# qec_pcb_v4.net
KiCad netlist of a schematic drawn in EAGLE
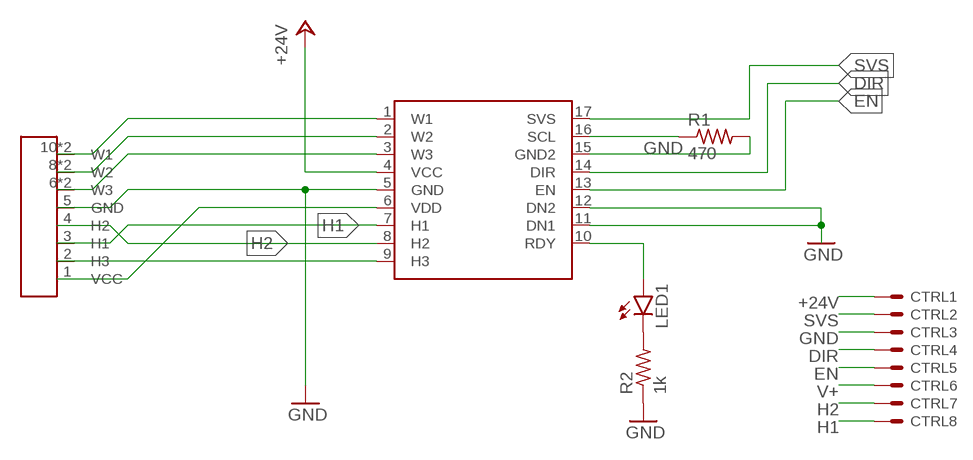
[diagram p0: schematic, sheet 1]

(export (version "E")
  (design (tool "Eeschema 10.0.6"))
  (components
    (comp (ref "CTRL")
      (value "JST8")
      (footprint "eagle-import:JST")
      (libsource (lib "eagle-import") (part "JST8"))
    )
    (comp (ref "DEC")
      (value "1-Q-EC1-Q-EC-SMD")
      (footprint "eagle-import:1-Q-EC-SMD")
      (libsource (lib "eagle-import") (part "1-Q-EC1-Q-EC-SMD"))
    )
    (comp (ref "LED1")
      (value "LEDCHIPLED_0805")
      (footprint "eagle-import:CHIPLED_0805")
      (libsource (lib "eagle-import") (part "LEDCHIPLED_0805"))
    )
    (comp (ref "MOTOR")
      (value "68611114122")
      (footprint "eagle-import:68611114122")
      (libsource (lib "eagle-import") (part "68611114122"))
    )
    (comp (ref "R1")
      (value "470")
      (footprint "eagle-import:M0805")
      (libsource (lib "eagle-import") (part "R-US_M0805"))
    )
    (comp (ref "R2")
      (value "1k")
      (footprint "eagle-import:M0805")
      (libsource (lib "eagle-import") (part "R-US_M0805"))
    )
  )
  (nets
    (net (code "1") (name "+24V") (class "Default")
      (node (ref "CTRL") (pin "1") (pinfunction "S_1") (pintype "passive"))
      (node (ref "DEC") (pin "4") (pinfunction "VCC_4") (pintype "bidirectional"))
    )
    (net (code "2") (name "/V+") (class "Default")
      (node (ref "CTRL") (pin "6") (pinfunction "S_6") (pintype "passive"))
      (node (ref "DEC") (pin "6") (pinfunction "VDD_6") (pintype "bidirectional"))
      (node (ref "MOTOR") (pin "1") (pinfunction "VCC_1") (pintype "bidirectional"))
    )
    (net (code "3") (name "DIR") (class "Default")
      (node (ref "CTRL") (pin "4") (pinfunction "S_4") (pintype "passive"))
      (node (ref "DEC") (pin "14") (pinfunction "DIR_14") (pintype "bidirectional"))
    )
    (net (code "4") (name "EN") (class "Default")
      (node (ref "CTRL") (pin "5") (pinfunction "S_5") (pintype "passive"))
      (node (ref "DEC") (pin "13") (pinfunction "EN_13") (pintype "bidirectional"))
    )
    (net (code "5") (name "GND") (class "Default")
      (node (ref "CTRL") (pin "3") (pinfunction "S_3") (pintype "passive"))
      (node (ref "DEC") (pin "11") (pinfunction "DN1_11") (pintype "bidirectional"))
      (node (ref "DEC") (pin "12") (pinfunction "DN2_12") (pintype "bidirectional"))
      (node (ref "DEC") (pin "15") (pinfunction "GND2_15") (pintype "bidirectional"))
      (node (ref "DEC") (pin "5") (pinfunction "GND_5") (pintype "bidirectional"))
      (node (ref "MOTOR") (pin "5") (pinfunction "GND_5") (pintype "bidirectional"))
      (node (ref "R1") (pin "2") (pinfunction "2_2") (pintype "passive"))
      (node (ref "R2") (pin "1") (pinfunction "1_1") (pintype "passive"))
    )
    (net (code "6") (name "H1") (class "Default")
      (node (ref "CTRL") (pin "8") (pinfunction "S_8") (pintype "passive"))
      (node (ref "DEC") (pin "7") (pinfunction "H1_7") (pintype "bidirectional"))
      (node (ref "MOTOR") (pin "3") (pinfunction "H1_3") (pintype "bidirectional"))
    )
    (net (code "7") (name "H2") (class "Default")
      (node (ref "CTRL") (pin "7") (pinfunction "S_7") (pintype "passive"))
      (node (ref "DEC") (pin "8") (pinfunction "H2_8") (pintype "bidirectional"))
      (node (ref "MOTOR") (pin "4") (pinfunction "H2_4") (pintype "bidirectional"))
    )
    (net (code "8") (name "Net-(DEC-H3)") (class "Default")
      (node (ref "DEC") (pin "9") (pinfunction "H3_9") (pintype "bidirectional"))
      (node (ref "MOTOR") (pin "2") (pinfunction "H3_2") (pintype "bidirectional"))
    )
    (net (code "9") (name "Net-(DEC-RDY)") (class "Default")
      (node (ref "DEC") (pin "10") (pinfunction "RDY_10") (pintype "bidirectional"))
      (node (ref "LED1") (pin "A") (pinfunction "A_A") (pintype "passive"))
    )
    (net (code "10") (name "Net-(DEC-SCL)") (class "Default")
      (node (ref "DEC") (pin "16") (pinfunction "SCL_16") (pintype "bidirectional"))
      (node (ref "R1") (pin "1") (pinfunction "1_1") (pintype "passive"))
    )
    (net (code "11") (name "Net-(DEC-W1)") (class "Default")
      (node (ref "DEC") (pin "1") (pinfunction "W1_1") (pintype "bidirectional"))
      (node (ref "MOTOR") (pin "10") (pinfunction "W1_10") (pintype "bidirectional"))
      (node (ref "MOTOR") (pin "11") (pinfunction "W1_11") (pintype "bidirectional"))
    )
    (net (code "12") (name "Net-(DEC-W2)") (class "Default")
      (node (ref "DEC") (pin "2") (pinfunction "W2_2") (pintype "bidirectional"))
      (node (ref "MOTOR") (pin "8") (pinfunction "W2_8") (pintype "bidirectional"))
      (node (ref "MOTOR") (pin "9") (pinfunction "W2_9") (pintype "bidirectional"))
    )
    (net (code "13") (name "Net-(DEC-W3)") (class "Default")
      (node (ref "DEC") (pin "3") (pinfunction "W3_3") (pintype "bidirectional"))
      (node (ref "MOTOR") (pin "6") (pinfunction "W3_6") (pintype "bidirectional"))
      (node (ref "MOTOR") (pin "7") (pinfunction "W3_7") (pintype "bidirectional"))
    )
    (net (code "14") (name "Net-(LED1-PadC)") (class "Default")
      (node (ref "LED1") (pin "C") (pinfunction "C_C") (pintype "passive"))
      (node (ref "R2") (pin "2") (pinfunction "2_2") (pintype "passive"))
    )
    (net (code "15") (name "SVS") (class "Default")
      (node (ref "CTRL") (pin "2") (pinfunction "S_2") (pintype "passive"))
      (node (ref "DEC") (pin "17") (pinfunction "SVS_17") (pintype "bidirectional"))
    )
  )
)
